# explorator_mainboard_v2_58mm.net
KiCad netlist of a schematic drawn in EAGLE
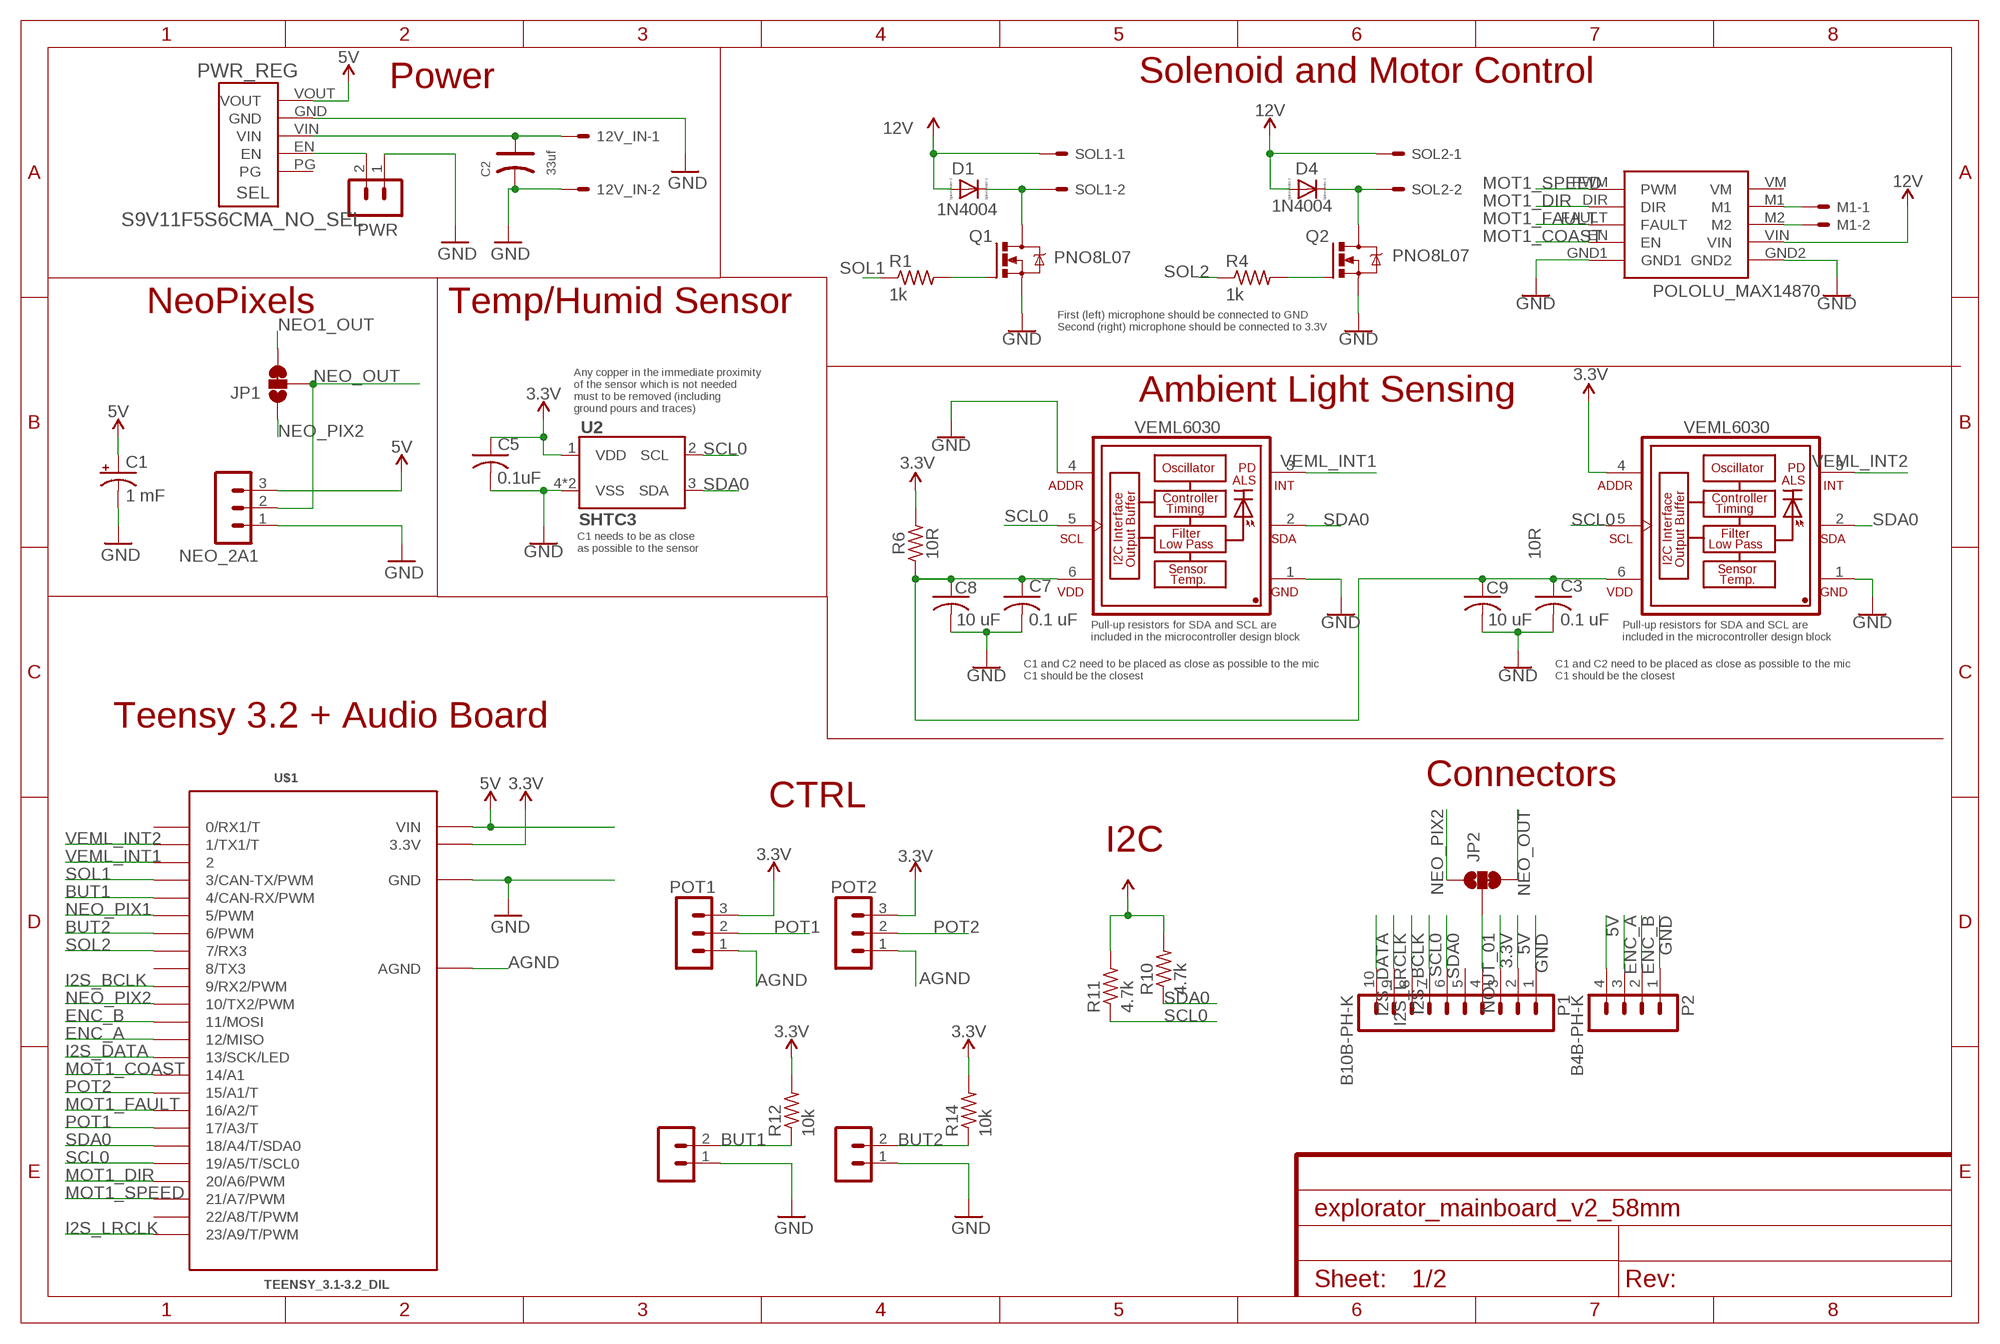
[diagram p0: schematic, sheet 1]
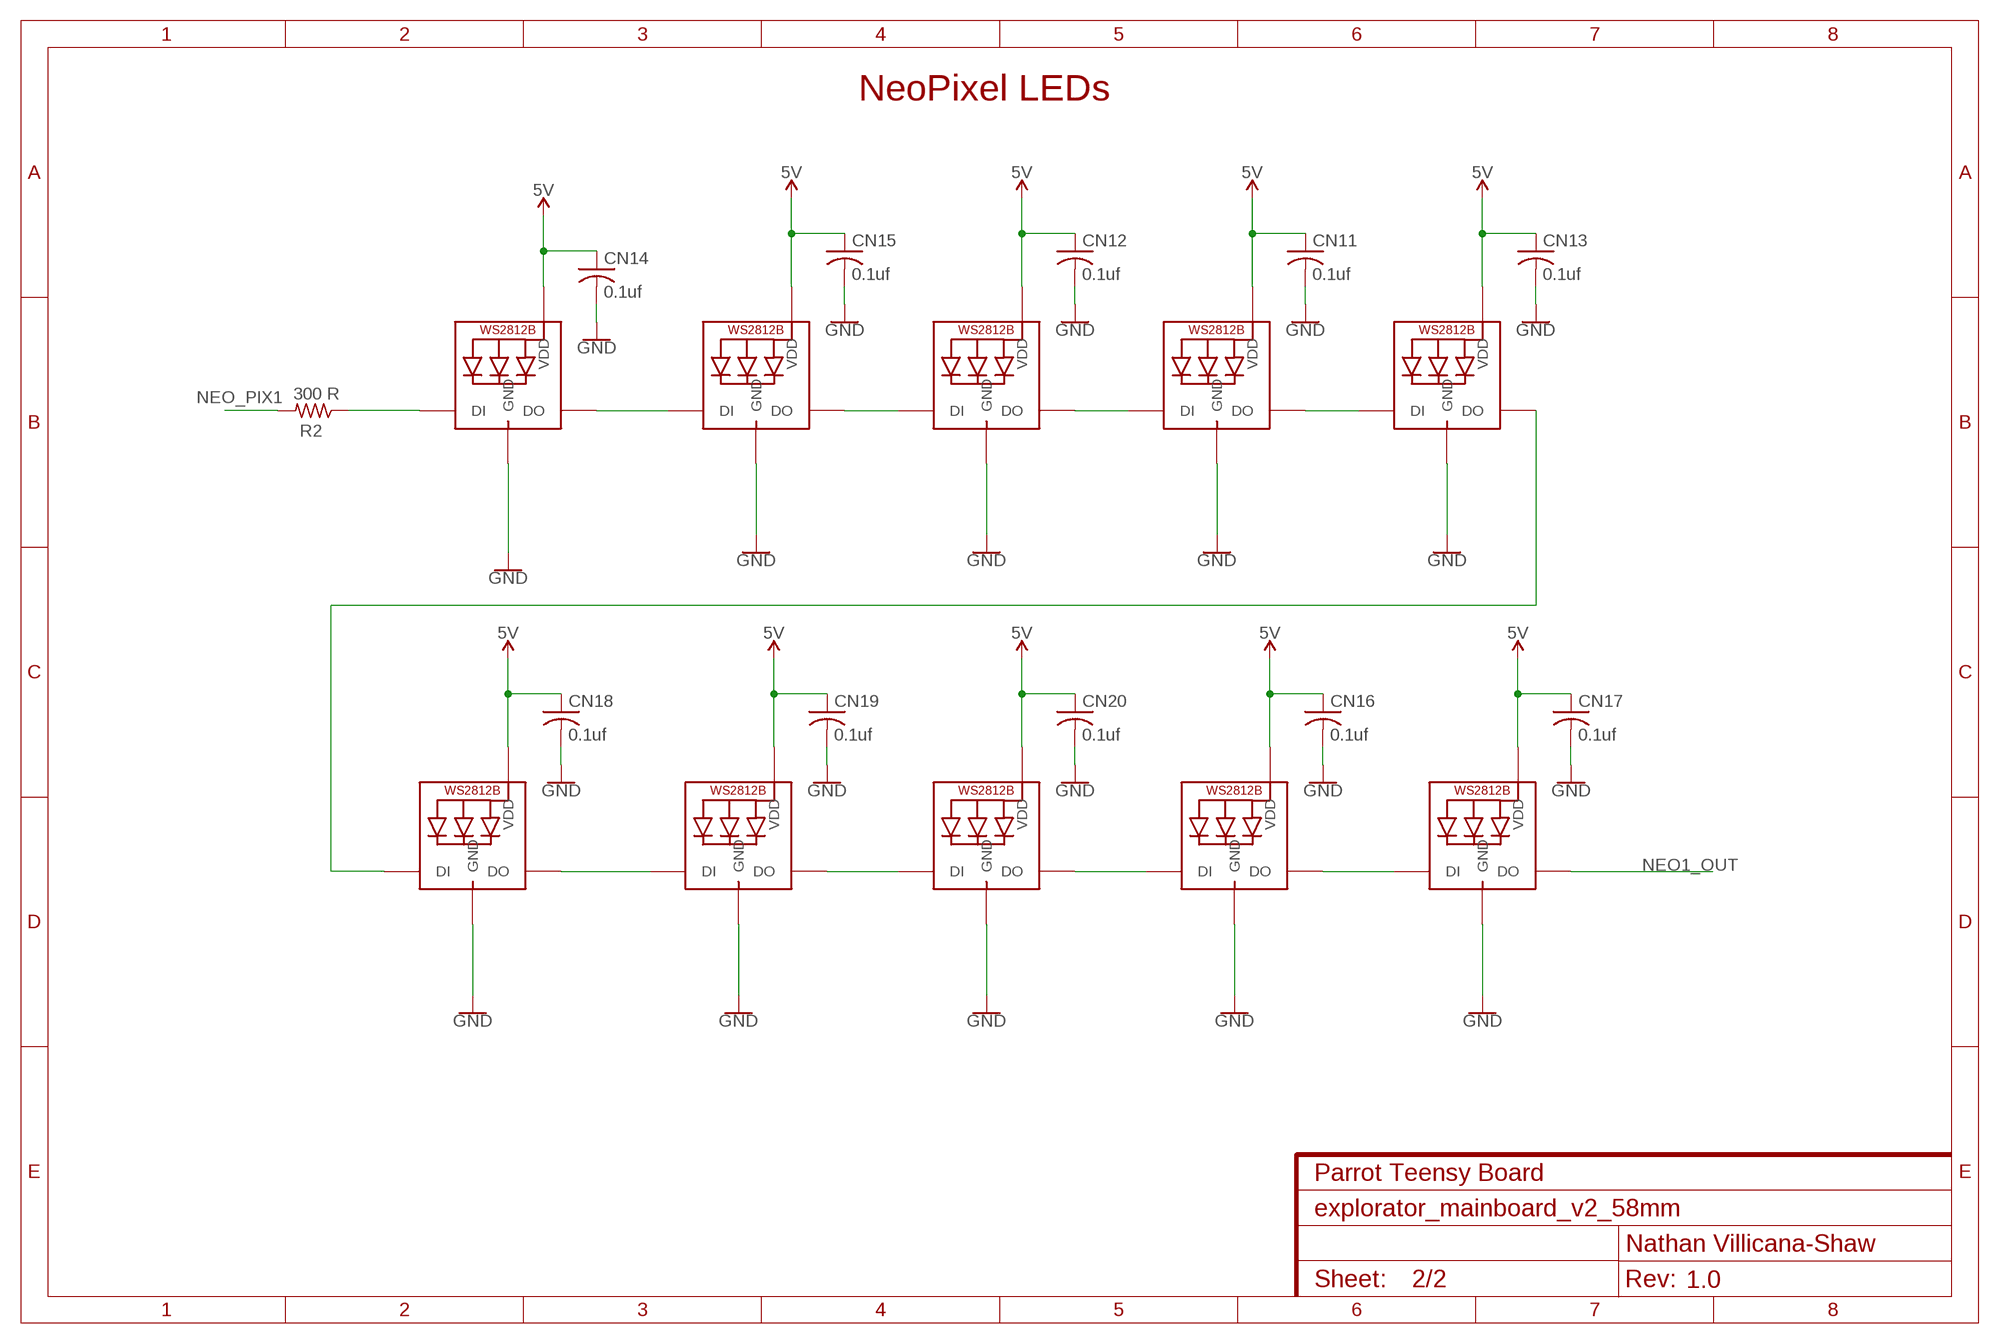
[diagram p1: schematic, sheet 2]

(export (version "E")
  (design (tool "Eeschema 10.0.6"))
  (components
    (comp (ref "12V_IN")
      (value "5566-2")
      (footprint "eagle-import:5566-2")
      (fields (field (name "MF") "MOLEX"))
      (libsource (lib "eagle-import") (part "5566-2"))
    )
    (comp (ref "BUT1")
      (value "B2B-PH-K")
      (footprint "eagle-import:B2B-PH-K")
      (libsource (lib "eagle-import") (part "B2B-PH-K"))
    )
    (comp (ref "BUT2")
      (value "B2B-PH-K")
      (footprint "eagle-import:B2B-PH-K")
      (libsource (lib "eagle-import") (part "B2B-PH-K"))
    )
    (comp (ref "C1")
      (value "1 mF")
      (footprint "eagle-import:UD-10X10_NICHICON")
      (libsource (lib "eagle-import") (part "CPOL-USUD-10X10"))
    )
    (comp (ref "C2")
      (value "33uf")
      (footprint "eagle-import:PC-D5.3MM")
      (fields (field (name "MPN") "KS 100uF/16V"))
      (libsource (lib "eagle-import") (part "DIP-ALUMINUM-47UF-16V(D5-H7MM)"))
    )
    (comp (ref "C3")
      (value "0.1 uF")
      (footprint "eagle-import:C0805")
      (libsource (lib "eagle-import") (part "C-USC0805"))
    )
    (comp (ref "C5")
      (value "0.1uF")
      (footprint "eagle-import:C0805")
      (libsource (lib "eagle-import") (part "C-USC0805"))
    )
    (comp (ref "C7")
      (value "0.1 uF")
      (footprint "eagle-import:C0805")
      (libsource (lib "eagle-import") (part "C-USC0805"))
    )
    (comp (ref "C8")
      (value "10 uF")
      (footprint "eagle-import:C0805")
      (libsource (lib "eagle-import") (part "C-USC0805"))
    )
    (comp (ref "C9")
      (value "10 uF")
      (footprint "eagle-import:C0805")
      (libsource (lib "eagle-import") (part "C-USC0805"))
    )
    (comp (ref "D1")
      (value "1N4004")
      (footprint "eagle-import:DIODE_DO35-7")
      (libsource (lib "eagle-import") (part "DIODE_E-DO35-7"))
    )
    (comp (ref "D4")
      (value "1N4004")
      (footprint "eagle-import:DIODE_DO35-7")
      (libsource (lib "eagle-import") (part "DIODE_E-DO35-7"))
    )
    (comp (ref "JP1")
      (value "JUMPER-SMT_3_1-NC_TRACE_SILK")
      (footprint "eagle-import:SMT-JUMPER_3_1-NC_TRACE_SILK")
      (libsource (lib "eagle-import") (part "JUMPER-SMT_3_1-NC_TRACE_SILK"))
    )
    (comp (ref "JP2")
      (value "JUMPER-SMT_3_1-NC_TRACE_SILK")
      (footprint "eagle-import:SMT-JUMPER_3_1-NC_TRACE_SILK")
      (libsource (lib "eagle-import") (part "JUMPER-SMT_3_1-NC_TRACE_SILK"))
    )
    (comp (ref "M1")
      (value "5566-2")
      (footprint "eagle-import:5566-2")
      (fields (field (name "MF") "MOLEX"))
      (libsource (lib "eagle-import") (part "5566-2"))
    )
    (comp (ref "MOT1")
      (value "POLOLU_MAX14870")
      (footprint "eagle-import:POLOLU_MAX14870")
      (libsource (lib "eagle-import") (part "POLOLU_MAX14870"))
    )
    (comp (ref "NEO_2A1")
      (value "B3B-PH-K")
      (footprint "eagle-import:B3B-PH-K")
      (libsource (lib "eagle-import") (part "B3B-PH-K"))
    )
    (comp (ref "P1")
      (value "B10B-PH-K")
      (footprint "eagle-import:B10B-PH-K")
      (libsource (lib "eagle-import") (part "B10B-PH-K"))
    )
    (comp (ref "P2")
      (value "B4B-PH-K")
      (footprint "eagle-import:B4B-PH-K")
      (libsource (lib "eagle-import") (part "B4B-PH-K"))
    )
    (comp (ref "POT1")
      (value "B3B-PH-K")
      (footprint "eagle-import:B3B-PH-K")
      (libsource (lib "eagle-import") (part "B3B-PH-K"))
    )
    (comp (ref "POT2")
      (value "B3B-PH-K")
      (footprint "eagle-import:B3B-PH-K")
      (libsource (lib "eagle-import") (part "B3B-PH-K"))
    )
    (comp (ref "PWR")
      (value "B2B-PH-K")
      (footprint "eagle-import:B2B-PH-K")
      (libsource (lib "eagle-import") (part "B2B-PH-K"))
    )
    (comp (ref "PWR_REG")
      (value "S9V11F5S6CMA_NO_SEL")
      (footprint "eagle-import:S9V11F3S5CMA_NO_SEL")
      (libsource (lib "eagle-import") (part "S9V11F5S6CMA_NO_SEL"))
    )
    (comp (ref "Q1")
      (value "PNO8L07")
      (footprint "eagle-import:TO220BV")
      (libsource (lib "eagle-import") (part "IRF540"))
    )
    (comp (ref "Q2")
      (value "PNO8L07")
      (footprint "eagle-import:TO220BV")
      (libsource (lib "eagle-import") (part "IRF540"))
    )
    (comp (ref "R1")
      (value "1k")
      (footprint "eagle-import:R0805")
      (libsource (lib "eagle-import") (part "rcl_334_R-US_R0805"))
    )
    (comp (ref "R4")
      (value "1k")
      (footprint "eagle-import:R0805")
      (libsource (lib "eagle-import") (part "rcl_334_R-US_R0805"))
    )
    (comp (ref "R6")
      (value "10 R")
      (footprint "eagle-import:R0805")
      (libsource (lib "eagle-import") (part "R-US_R0805"))
    )
    (comp (ref "R10")
      (value "4.7k")
      (footprint "eagle-import:R0805")
      (libsource (lib "eagle-import") (part "rcl_334_R-US_R0805"))
    )
    (comp (ref "R11")
      (value "4.7k")
      (footprint "eagle-import:R0805")
      (libsource (lib "eagle-import") (part "rcl_334_R-US_R0805"))
    )
    (comp (ref "R12")
      (value "10k")
      (footprint "eagle-import:R0805")
      (libsource (lib "eagle-import") (part "rcl_334_R-US_R0805"))
    )
    (comp (ref "R14")
      (value "10k")
      (footprint "eagle-import:R0805")
      (libsource (lib "eagle-import") (part "rcl_334_R-US_R0805"))
    )
    (comp (ref "SOL1")
      (value "5566-2")
      (footprint "eagle-import:5566-2")
      (fields (field (name "MF") "MOLEX"))
      (libsource (lib "eagle-import") (part "5566-2"))
    )
    (comp (ref "SOL2")
      (value "5566-2")
      (footprint "eagle-import:5566-2")
      (fields (field (name "MF") "MOLEX"))
      (libsource (lib "eagle-import") (part "5566-2"))
    )
    (comp (ref "U$1")
      (value "TEENSY_3.1-3.2_DIL")
      (footprint "eagle-import:TEENSY_3.0-3.2&LC_DIL")
      (libsource (lib "eagle-import") (part "TEENSY_3.1-3.2_DIL"))
    )
    (comp (ref "U2")
      (value "SHTC3")
      (footprint "eagle-import:SHTC3")
      (libsource (lib "eagle-import") (part "SHTC3"))
    )
    (comp (ref "VMEL1")
      (value "VEML6030")
      (footprint "eagle-import:VISHAY_VEML6030_2X2X0.87")
      (fields (field (name "MF") "Vishay Semiconductor") (field (name "MP") "VEML6030-GS15"))
      (libsource (lib "eagle-import") (part "VEML6030-GS15"))
    )
    (comp (ref "VMEL2")
      (value "VEML6030")
      (footprint "eagle-import:VISHAY_VEML6030_2X2X0.87")
      (fields (field (name "MF") "Vishay Semiconductor") (field (name "MP") "VEML6030-GS15"))
      (libsource (lib "eagle-import") (part "VEML6030-GS15"))
    )
    (comp (ref "CN11")
      (value "0.1uf")
      (footprint "eagle-import:C0805K")
      (libsource (lib "eagle-import") (part "resistor_348_C-USC0805K"))
    )
    (comp (ref "CN12")
      (value "0.1uf")
      (footprint "eagle-import:C0805K")
      (libsource (lib "eagle-import") (part "resistor_348_C-USC0805K"))
    )
    (comp (ref "CN13")
      (value "0.1uf")
      (footprint "eagle-import:C0805K")
      (libsource (lib "eagle-import") (part "resistor_348_C-USC0805K"))
    )
    (comp (ref "CN14")
      (value "0.1uf")
      (footprint "eagle-import:C0805K")
      (libsource (lib "eagle-import") (part "resistor_348_C-USC0805K"))
    )
    (comp (ref "CN15")
      (value "0.1uf")
      (footprint "eagle-import:C0805K")
      (libsource (lib "eagle-import") (part "resistor_348_C-USC0805K"))
    )
    (comp (ref "CN16")
      (value "0.1uf")
      (footprint "eagle-import:C0805K")
      (libsource (lib "eagle-import") (part "resistor_348_C-USC0805K"))
    )
    (comp (ref "CN17")
      (value "0.1uf")
      (footprint "eagle-import:C0805K")
      (libsource (lib "eagle-import") (part "resistor_348_C-USC0805K"))
    )
    (comp (ref "CN18")
      (value "0.1uf")
      (footprint "eagle-import:C0805K")
      (libsource (lib "eagle-import") (part "resistor_348_C-USC0805K"))
    )
    (comp (ref "CN19")
      (value "0.1uf")
      (footprint "eagle-import:C0805K")
      (libsource (lib "eagle-import") (part "resistor_348_C-USC0805K"))
    )
    (comp (ref "CN20")
      (value "0.1uf")
      (footprint "eagle-import:C0805K")
      (libsource (lib "eagle-import") (part "resistor_348_C-USC0805K"))
    )
    (comp (ref "NEO11")
      (value "WS2812B5050")
      (footprint "eagle-import:WS2812B")
      (libsource (lib "eagle-import") (part "WS2812B5050"))
    )
    (comp (ref "NEO12")
      (value "WS2812B5050")
      (footprint "eagle-import:WS2812B")
      (libsource (lib "eagle-import") (part "WS2812B5050"))
    )
    (comp (ref "NEO13")
      (value "WS2812B5050")
      (footprint "eagle-import:WS2812B")
      (libsource (lib "eagle-import") (part "WS2812B5050"))
    )
    (comp (ref "NEO14")
      (value "WS2812B5050")
      (footprint "eagle-import:WS2812B")
      (libsource (lib "eagle-import") (part "WS2812B5050"))
    )
    (comp (ref "NEO15")
      (value "WS2812B5050")
      (footprint "eagle-import:WS2812B")
      (libsource (lib "eagle-import") (part "WS2812B5050"))
    )
    (comp (ref "NEO16")
      (value "WS2812B5050")
      (footprint "eagle-import:WS2812B")
      (libsource (lib "eagle-import") (part "WS2812B5050"))
    )
    (comp (ref "NEO17")
      (value "WS2812B5050")
      (footprint "eagle-import:WS2812B")
      (libsource (lib "eagle-import") (part "WS2812B5050"))
    )
    (comp (ref "NEO18")
      (value "WS2812B5050")
      (footprint "eagle-import:WS2812B")
      (libsource (lib "eagle-import") (part "WS2812B5050"))
    )
    (comp (ref "NEO19")
      (value "WS2812B5050")
      (footprint "eagle-import:WS2812B")
      (libsource (lib "eagle-import") (part "WS2812B5050"))
    )
    (comp (ref "NEO20")
      (value "WS2812B5050")
      (footprint "eagle-import:WS2812B")
      (libsource (lib "eagle-import") (part "WS2812B5050"))
    )
    (comp (ref "R2")
      (value "300 R")
      (footprint "eagle-import:R0805")
      (libsource (lib "eagle-import") (part "R-US_R0805"))
    )
  )
  (nets
    (net (code "1") (name "3.3V") (class "Default")
      (node (ref "C5") (pin "1") (pinfunction "1_1") (pintype "passive"))
      (node (ref "P1") (pin "3") (pinfunction "3_3") (pintype "passive"))
      (node (ref "POT1") (pin "3") (pinfunction "3_3") (pintype "passive"))
      (node (ref "POT2") (pin "3") (pinfunction "3_3") (pintype "passive"))
      (node (ref "R10") (pin "2") (pinfunction "2_2") (pintype "passive"))
      (node (ref "R11") (pin "2") (pinfunction "2_2") (pintype "passive"))
      (node (ref "R12") (pin "2") (pinfunction "2_2") (pintype "passive"))
      (node (ref "R14") (pin "2") (pinfunction "2_2") (pintype "passive"))
      (node (ref "R6") (pin "2") (pinfunction "2_2") (pintype "passive"))
      (node (ref "U$1") (pin "3.3V") (pinfunction "3.3V_3.3V") (pintype "power_in"))
      (node (ref "U2") (pin "1") (pinfunction "VDD_1") (pintype "bidirectional"))
      (node (ref "VMEL2") (pin "4") (pinfunction "ADDR_4") (pintype "bidirectional"))
    )
    (net (code "2") (name "5V") (class "Default")
      (node (ref "C1") (pin "+") (pinfunction "+_+") (pintype "passive"))
      (node (ref "CN11") (pin "1") (pinfunction "1_1") (pintype "passive"))
      (node (ref "CN12") (pin "1") (pinfunction "1_1") (pintype "passive"))
      (node (ref "CN13") (pin "1") (pinfunction "1_1") (pintype "passive"))
      (node (ref "CN14") (pin "1") (pinfunction "1_1") (pintype "passive"))
      (node (ref "CN15") (pin "1") (pinfunction "1_1") (pintype "passive"))
      (node (ref "CN16") (pin "1") (pinfunction "1_1") (pintype "passive"))
      (node (ref "CN17") (pin "1") (pinfunction "1_1") (pintype "passive"))
      (node (ref "CN18") (pin "1") (pinfunction "1_1") (pintype "passive"))
      (node (ref "CN19") (pin "1") (pinfunction "1_1") (pintype "passive"))
      (node (ref "CN20") (pin "1") (pinfunction "1_1") (pintype "passive"))
      (node (ref "NEO11") (pin "1-VDD") (pinfunction "VDD_1-VDD") (pintype "power_in"))
      (node (ref "NEO12") (pin "1-VDD") (pinfunction "VDD_1-VDD") (pintype "power_in"))
      (node (ref "NEO13") (pin "1-VDD") (pinfunction "VDD_1-VDD") (pintype "power_in"))
      (node (ref "NEO14") (pin "1-VDD") (pinfunction "VDD_1-VDD") (pintype "power_in"))
      (node (ref "NEO15") (pin "1-VDD") (pinfunction "VDD_1-VDD") (pintype "power_in"))
      (node (ref "NEO16") (pin "1-VDD") (pinfunction "VDD_1-VDD") (pintype "power_in"))
      (node (ref "NEO17") (pin "1-VDD") (pinfunction "VDD_1-VDD") (pintype "power_in"))
      (node (ref "NEO18") (pin "1-VDD") (pinfunction "VDD_1-VDD") (pintype "power_in"))
      (node (ref "NEO19") (pin "1-VDD") (pinfunction "VDD_1-VDD") (pintype "power_in"))
      (node (ref "NEO20") (pin "1-VDD") (pinfunction "VDD_1-VDD") (pintype "power_in"))
      (node (ref "NEO_2A1") (pin "3") (pinfunction "3_3") (pintype "passive"))
      (node (ref "P1") (pin "2") (pinfunction "2_2") (pintype "passive"))
      (node (ref "P2") (pin "4") (pinfunction "4_4") (pintype "passive"))
      (node (ref "PWR_REG") (pin "VOUT") (pinfunction "VOUT_VOUT") (pintype "bidirectional"))
      (node (ref "U$1") (pin "VIN") (pinfunction "VIN_VIN") (pintype "power_in"))
    )
    (net (code "3") (name "12V") (class "Default")
      (node (ref "12V_IN") (pin "1") (pinfunction "S_1") (pintype "passive"))
      (node (ref "C2") (pin "+") (pinfunction "+_+") (pintype "passive"))
      (node (ref "D1") (pin "A") (pinfunction "C_A") (pintype "passive"))
      (node (ref "D4") (pin "A") (pinfunction "C_A") (pintype "passive"))
      (node (ref "MOT1") (pin "VIN") (pinfunction "VIN_VIN") (pintype "bidirectional"))
      (node (ref "PWR_REG") (pin "VIN") (pinfunction "VIN_VIN") (pintype "bidirectional"))
      (node (ref "SOL1") (pin "1") (pinfunction "S_1") (pintype "passive"))
      (node (ref "SOL2") (pin "1") (pinfunction "S_1") (pintype "passive"))
    )
    (net (code "4") (name "AGND") (class "Default")
      (node (ref "POT1") (pin "1") (pinfunction "1_1") (pintype "passive"))
      (node (ref "POT2") (pin "1") (pinfunction "1_1") (pintype "passive"))
      (node (ref "U$1") (pin "AGND") (pinfunction "AGND_AGND") (pintype "power_in"))
    )
    (net (code "5") (name "BUT1") (class "Default")
      (node (ref "BUT1") (pin "2") (pinfunction "2_2") (pintype "passive"))
      (node (ref "R12") (pin "1") (pinfunction "1_1") (pintype "passive"))
      (node (ref "U$1") (pin "4") (pinfunction "4/CAN-RX/PWM_4") (pintype "bidirectional"))
    )
    (net (code "6") (name "BUT2") (class "Default")
      (node (ref "BUT2") (pin "2") (pinfunction "2_2") (pintype "passive"))
      (node (ref "R14") (pin "1") (pinfunction "1_1") (pintype "passive"))
      (node (ref "U$1") (pin "6") (pinfunction "6/PWM_6") (pintype "bidirectional"))
    )
    (net (code "7") (name "ENC_A") (class "Default")
      (node (ref "P2") (pin "3") (pinfunction "3_3") (pintype "passive"))
      (node (ref "U$1") (pin "12") (pinfunction "12/MISO_12") (pintype "bidirectional"))
    )
    (net (code "8") (name "ENC_B") (class "Default")
      (node (ref "P2") (pin "2") (pinfunction "2_2") (pintype "passive"))
      (node (ref "U$1") (pin "11") (pinfunction "11/MOSI_11") (pintype "bidirectional"))
    )
    (net (code "9") (name "GND") (class "Default")
      (node (ref "12V_IN") (pin "2") (pinfunction "S_2") (pintype "passive"))
      (node (ref "BUT1") (pin "1") (pinfunction "1_1") (pintype "passive"))
      (node (ref "BUT2") (pin "1") (pinfunction "1_1") (pintype "passive"))
      (node (ref "C1") (pin "-") (pinfunction "-_-") (pintype "passive"))
      (node (ref "C2") (pin "-") (pinfunction "-_-") (pintype "passive"))
      (node (ref "C3") (pin "2") (pinfunction "2_2") (pintype "passive"))
      (node (ref "C5") (pin "2") (pinfunction "2_2") (pintype "passive"))
      (node (ref "C7") (pin "2") (pinfunction "2_2") (pintype "passive"))
      (node (ref "C8") (pin "2") (pinfunction "2_2") (pintype "passive"))
      (node (ref "C9") (pin "2") (pinfunction "2_2") (pintype "passive"))
      (node (ref "CN11") (pin "2") (pinfunction "2_2") (pintype "passive"))
      (node (ref "CN12") (pin "2") (pinfunction "2_2") (pintype "passive"))
      (node (ref "CN13") (pin "2") (pinfunction "2_2") (pintype "passive"))
      (node (ref "CN14") (pin "2") (pinfunction "2_2") (pintype "passive"))
      (node (ref "CN15") (pin "2") (pinfunction "2_2") (pintype "passive"))
      (node (ref "CN16") (pin "2") (pinfunction "2_2") (pintype "passive"))
      (node (ref "CN17") (pin "2") (pinfunction "2_2") (pintype "passive"))
      (node (ref "CN18") (pin "2") (pinfunction "2_2") (pintype "passive"))
      (node (ref "CN19") (pin "2") (pinfunction "2_2") (pintype "passive"))
      (node (ref "CN20") (pin "2") (pinfunction "2_2") (pintype "passive"))
      (node (ref "MOT1") (pin "GND1") (pinfunction "GND1_GND1") (pintype "bidirectional"))
      (node (ref "MOT1") (pin "GND2") (pinfunction "GND2_GND2") (pintype "bidirectional"))
      (node (ref "NEO11") (pin "3-GND") (pinfunction "GND_3-GND") (pintype "power_in"))
      (node (ref "NEO12") (pin "3-GND") (pinfunction "GND_3-GND") (pintype "power_in"))
      (node (ref "NEO13") (pin "3-GND") (pinfunction "GND_3-GND") (pintype "power_in"))
      (node (ref "NEO14") (pin "3-GND") (pinfunction "GND_3-GND") (pintype "power_in"))
      (node (ref "NEO15") (pin "3-GND") (pinfunction "GND_3-GND") (pintype "power_in"))
      (node (ref "NEO16") (pin "3-GND") (pinfunction "GND_3-GND") (pintype "power_in"))
      (node (ref "NEO17") (pin "3-GND") (pinfunction "GND_3-GND") (pintype "power_in"))
      (node (ref "NEO18") (pin "3-GND") (pinfunction "GND_3-GND") (pintype "power_in"))
      (node (ref "NEO19") (pin "3-GND") (pinfunction "GND_3-GND") (pintype "power_in"))
      (node (ref "NEO20") (pin "3-GND") (pinfunction "GND_3-GND") (pintype "power_in"))
      (node (ref "NEO_2A1") (pin "1") (pinfunction "1_1") (pintype "passive"))
      (node (ref "P1") (pin "1") (pinfunction "1_1") (pintype "passive"))
      (node (ref "P2") (pin "1") (pinfunction "1_1") (pintype "passive"))
      (node (ref "PWR") (pin "1") (pinfunction "1_1") (pintype "passive"))
      (node (ref "PWR_REG") (pin "GND") (pinfunction "GND_GND") (pintype "bidirectional"))
      (node (ref "Q1") (pin "S") (pinfunction "S_S") (pintype "passive"))
      (node (ref "Q2") (pin "S") (pinfunction "S_S") (pintype "passive"))
      (node (ref "U$1") (pin "GND") (pinfunction "GND_GND") (pintype "power_in"))
      (node (ref "U2") (pin "4") (pinfunction "VSS_4") (pintype "bidirectional"))
      (node (ref "U2") (pin "5") (pinfunction "VSS_5") (pintype "bidirectional"))
      (node (ref "VMEL1") (pin "1") (pinfunction "GND_1") (pintype "power_in"))
      (node (ref "VMEL1") (pin "4") (pinfunction "ADDR_4") (pintype "bidirectional"))
      (node (ref "VMEL2") (pin "1") (pinfunction "GND_1") (pintype "power_in"))
    )
    (net (code "10") (name "I2S_BCLK") (class "Default")
      (node (ref "P1") (pin "8") (pinfunction "8_8") (pintype "passive"))
      (node (ref "U$1") (pin "9") (pinfunction "9/RX2/PWM_9") (pintype "bidirectional"))
    )
    (net (code "11") (name "I2S_DATA") (class "Default")
      (node (ref "P1") (pin "10") (pinfunction "10_10") (pintype "passive"))
      (node (ref "U$1") (pin "13") (pinfunction "13/SCK/LED_13") (pintype "bidirectional"))
    )
    (net (code "12") (name "I2S_LRCLK") (class "Default")
      (node (ref "P1") (pin "9") (pinfunction "9_9") (pintype "passive"))
      (node (ref "U$1") (pin "23/A9") (pinfunction "23/A9/T/PWM_23/A9") (pintype "bidirectional"))
    )
    (net (code "13") (name "MOT1_COAST") (class "Default")
      (node (ref "MOT1") (pin "EN") (pinfunction "EN_EN") (pintype "bidirectional"))
      (node (ref "U$1") (pin "14/A0") (pinfunction "14/A1_14/A0") (pintype "bidirectional"))
    )
    (net (code "14") (name "MOT1_DIR") (class "Default")
      (node (ref "MOT1") (pin "DIR") (pinfunction "DIR_DIR") (pintype "bidirectional"))
      (node (ref "U$1") (pin "20/A6") (pinfunction "20/A6/PWM_20/A6") (pintype "bidirectional"))
    )
    (net (code "15") (name "MOT1_FAULT") (class "Default")
      (node (ref "MOT1") (pin "FAULT") (pinfunction "FAULT_FAULT") (pintype "bidirectional"))
      (node (ref "U$1") (pin "16/A2") (pinfunction "16/A2/T_16/A2") (pintype "bidirectional"))
    )
    (net (code "16") (name "MOT1_SPEED") (class "Default")
      (node (ref "MOT1") (pin "PWM") (pinfunction "PWM_PWM") (pintype "bidirectional"))
      (node (ref "U$1") (pin "21/A7") (pinfunction "21/A7/PWM_21/A7") (pintype "bidirectional"))
    )
    (net (code "17") (name "NEO1_OUT") (class "Default")
      (node (ref "JP1") (pin "3") (pinfunction "3_3") (pintype "passive"))
      (node (ref "NEO17") (pin "2-DOUT") (pinfunction "DO_2-DOUT") (pintype "output"))
    )
    (net (code "18") (name "NEO_OUT") (class "Default")
      (node (ref "JP1") (pin "2") (pinfunction "2_2") (pintype "passive"))
      (node (ref "JP2") (pin "3") (pinfunction "3_3") (pintype "passive"))
      (node (ref "NEO_2A1") (pin "2") (pinfunction "2_2") (pintype "passive"))
    )
    (net (code "19") (name "NEO_PIX1") (class "Default")
      (node (ref "R2") (pin "2") (pinfunction "2_2") (pintype "passive"))
      (node (ref "U$1") (pin "5") (pinfunction "5/PWM_5") (pintype "bidirectional"))
    )
    (net (code "20") (name "NEO_PIX2") (class "Default")
      (node (ref "JP1") (pin "1") (pinfunction "1_1") (pintype "passive"))
      (node (ref "JP2") (pin "1") (pinfunction "1_1") (pintype "passive"))
      (node (ref "U$1") (pin "10") (pinfunction "10/TX2/PWM_10") (pintype "bidirectional"))
    )
    (net (code "21") (name "NOUT_01") (class "Default")
      (node (ref "JP2") (pin "2") (pinfunction "2_2") (pintype "passive"))
      (node (ref "P1") (pin "4") (pinfunction "4_4") (pintype "passive"))
    )
    (net (code "22") (name "Net-(D1-A)") (class "Default")
      (node (ref "D1") (pin "C") (pinfunction "A_C") (pintype "passive"))
      (node (ref "Q1") (pin "D") (pinfunction "D_D") (pintype "passive"))
      (node (ref "SOL1") (pin "2") (pinfunction "S_2") (pintype "passive"))
    )
    (net (code "23") (name "Net-(D4-A)") (class "Default")
      (node (ref "D4") (pin "C") (pinfunction "A_C") (pintype "passive"))
      (node (ref "Q2") (pin "D") (pinfunction "D_D") (pintype "passive"))
      (node (ref "SOL2") (pin "2") (pinfunction "S_2") (pintype "passive"))
    )
    (net (code "24") (name "Net-(M1A-S)") (class "Default")
      (node (ref "M1") (pin "1") (pinfunction "S_1") (pintype "passive"))
      (node (ref "MOT1") (pin "M1") (pinfunction "M1_M1") (pintype "bidirectional"))
    )
    (net (code "25") (name "Net-(M1B-S)") (class "Default")
      (node (ref "M1") (pin "2") (pinfunction "S_2") (pintype "passive"))
      (node (ref "MOT1") (pin "M2") (pinfunction "M2_M2") (pintype "bidirectional"))
    )
    (net (code "26") (name "Net-(NEO11-DI)") (class "Default")
      (node (ref "NEO11") (pin "4-DIN") (pinfunction "DI_4-DIN") (pintype "input"))
      (node (ref "NEO12") (pin "2-DOUT") (pinfunction "DO_2-DOUT") (pintype "output"))
    )
    (net (code "27") (name "Net-(NEO11-DO)") (class "Default")
      (node (ref "NEO11") (pin "2-DOUT") (pinfunction "DO_2-DOUT") (pintype "output"))
      (node (ref "NEO13") (pin "4-DIN") (pinfunction "DI_4-DIN") (pintype "input"))
    )
    (net (code "28") (name "Net-(NEO12-DI)") (class "Default")
      (node (ref "NEO12") (pin "4-DIN") (pinfunction "DI_4-DIN") (pintype "input"))
      (node (ref "NEO15") (pin "2-DOUT") (pinfunction "DO_2-DOUT") (pintype "output"))
    )
    (net (code "29") (name "Net-(NEO13-DO)") (class "Default")
      (node (ref "NEO13") (pin "2-DOUT") (pinfunction "DO_2-DOUT") (pintype "output"))
      (node (ref "NEO18") (pin "4-DIN") (pinfunction "DI_4-DIN") (pintype "input"))
    )
    (net (code "30") (name "Net-(NEO14-DI)") (class "Default")
      (node (ref "NEO14") (pin "4-DIN") (pinfunction "DI_4-DIN") (pintype "input"))
      (node (ref "R2") (pin "1") (pinfunction "1_1") (pintype "passive"))
    )
    (net (code "31") (name "Net-(NEO14-DO)") (class "Default")
      (node (ref "NEO14") (pin "2-DOUT") (pinfunction "DO_2-DOUT") (pintype "output"))
      (node (ref "NEO15") (pin "4-DIN") (pinfunction "DI_4-DIN") (pintype "input"))
    )
    (net (code "32") (name "Net-(NEO16-DI)") (class "Default")
      (node (ref "NEO16") (pin "4-DIN") (pinfunction "DI_4-DIN") (pintype "input"))
      (node (ref "NEO20") (pin "2-DOUT") (pinfunction "DO_2-DOUT") (pintype "output"))
    )
    (net (code "33") (name "Net-(NEO16-DO)") (class "Default")
      (node (ref "NEO16") (pin "2-DOUT") (pinfunction "DO_2-DOUT") (pintype "output"))
      (node (ref "NEO17") (pin "4-DIN") (pinfunction "DI_4-DIN") (pintype "input"))
    )
    (net (code "34") (name "Net-(NEO18-DO)") (class "Default")
      (node (ref "NEO18") (pin "2-DOUT") (pinfunction "DO_2-DOUT") (pintype "output"))
      (node (ref "NEO19") (pin "4-DIN") (pinfunction "DI_4-DIN") (pintype "input"))
    )
    (net (code "35") (name "Net-(NEO19-DO)") (class "Default")
      (node (ref "NEO19") (pin "2-DOUT") (pinfunction "DO_2-DOUT") (pintype "output"))
      (node (ref "NEO20") (pin "4-DIN") (pinfunction "DI_4-DIN") (pintype "input"))
    )
    (net (code "36") (name "Net-(PWR-Pad2)") (class "Default")
      (node (ref "PWR") (pin "2") (pinfunction "2_2") (pintype "passive"))
      (node (ref "PWR_REG") (pin "EN") (pinfunction "EN_EN") (pintype "bidirectional"))
    )
    (net (code "37") (name "Net-(Q1-PadG)") (class "Default")
      (node (ref "Q1") (pin "G") (pinfunction "G_G") (pintype "passive"))
      (node (ref "R1") (pin "2") (pinfunction "2_2") (pintype "passive"))
    )
    (net (code "38") (name "Net-(Q2-PadG)") (class "Default")
      (node (ref "Q2") (pin "G") (pinfunction "G_G") (pintype "passive"))
      (node (ref "R4") (pin "2") (pinfunction "2_2") (pintype "passive"))
    )
    (net (code "39") (name "Net-(VMEL1-VDD)") (class "Default")
      (node (ref "C3") (pin "1") (pinfunction "1_1") (pintype "passive"))
      (node (ref "C7") (pin "1") (pinfunction "1_1") (pintype "passive"))
      (node (ref "C8") (pin "1") (pinfunction "1_1") (pintype "passive"))
      (node (ref "C9") (pin "1") (pinfunction "1_1") (pintype "passive"))
      (node (ref "R6") (pin "1") (pinfunction "1_1") (pintype "passive"))
      (node (ref "VMEL1") (pin "6") (pinfunction "VDD_6") (pintype "power_in"))
      (node (ref "VMEL2") (pin "6") (pinfunction "VDD_6") (pintype "power_in"))
    )
    (net (code "40") (name "POT1") (class "Default")
      (node (ref "POT1") (pin "2") (pinfunction "2_2") (pintype "passive"))
      (node (ref "U$1") (pin "17/A3") (pinfunction "17/A3/T_17/A3") (pintype "bidirectional"))
    )
    (net (code "41") (name "POT2") (class "Default")
      (node (ref "POT2") (pin "2") (pinfunction "2_2") (pintype "passive"))
      (node (ref "U$1") (pin "15/A1") (pinfunction "15/A1/T_15/A1") (pintype "bidirectional"))
    )
    (net (code "42") (name "SCL0") (class "Default")
      (node (ref "P1") (pin "7") (pinfunction "7_7") (pintype "passive"))
      (node (ref "R11") (pin "1") (pinfunction "1_1") (pintype "passive"))
      (node (ref "U$1") (pin "19/A5") (pinfunction "19/A5/T/SCL0_19/A5") (pintype "bidirectional"))
      (node (ref "U2") (pin "2") (pinfunction "SCL_2") (pintype "bidirectional"))
      (node (ref "VMEL1") (pin "5") (pinfunction "SCL_5") (pintype "input"))
      (node (ref "VMEL2") (pin "5") (pinfunction "SCL_5") (pintype "input"))
    )
    (net (code "43") (name "SDA0") (class "Default")
      (node (ref "P1") (pin "6") (pinfunction "6_6") (pintype "passive"))
      (node (ref "R10") (pin "1") (pinfunction "1_1") (pintype "passive"))
      (node (ref "U$1") (pin "18/A4") (pinfunction "18/A4/T/SDA0_18/A4") (pintype "bidirectional"))
      (node (ref "U2") (pin "3") (pinfunction "SDA_3") (pintype "bidirectional"))
      (node (ref "VMEL1") (pin "2") (pinfunction "SDA_2") (pintype "bidirectional"))
      (node (ref "VMEL2") (pin "2") (pinfunction "SDA_2") (pintype "bidirectional"))
    )
    (net (code "44") (name "SOL1") (class "Default")
      (node (ref "R1") (pin "1") (pinfunction "1_1") (pintype "passive"))
      (node (ref "U$1") (pin "3") (pinfunction "3/CAN-TX/PWM_3") (pintype "bidirectional"))
    )
    (net (code "45") (name "SOL2") (class "Default")
      (node (ref "R4") (pin "1") (pinfunction "1_1") (pintype "passive"))
      (node (ref "U$1") (pin "7") (pinfunction "7/RX3_7") (pintype "bidirectional"))
    )
    (net (code "46") (name "VEML_INT1") (class "Default")
      (node (ref "U$1") (pin "2") (pinfunction "2_2") (pintype "bidirectional"))
      (node (ref "VMEL1") (pin "3") (pinfunction "INT_3") (pintype "output"))
    )
    (net (code "47") (name "VEML_INT2") (class "Default")
      (node (ref "U$1") (pin "1") (pinfunction "1/TX1/T_1") (pintype "bidirectional"))
      (node (ref "VMEL2") (pin "3") (pinfunction "INT_3") (pintype "output"))
    )
    (net (code "48") (name "unconnected-(MOT1-PadVM)") (class "Default")
      (node (ref "MOT1") (pin "VM") (pinfunction "VM_VM") (pintype "bidirectional"))
    )
    (net (code "49") (name "unconnected-(P1-Pad5)") (class "Default")
      (node (ref "P1") (pin "5") (pinfunction "5_5") (pintype "passive"))
    )
    (net (code "50") (name "unconnected-(PWR_REG-PadPG)") (class "Default")
      (node (ref "PWR_REG") (pin "PG") (pinfunction "PG_PG") (pintype "bidirectional"))
    )
    (net (code "51") (name "unconnected-(U$1-0{slash}RX1{slash}T-Pad0)") (class "Default")
      (node (ref "U$1") (pin "0") (pinfunction "0/RX1/T_0") (pintype "bidirectional"))
    )
    (net (code "52") (name "unconnected-(U$1-8{slash}TX3-Pad8)") (class "Default")
      (node (ref "U$1") (pin "8") (pinfunction "8/TX3_8") (pintype "bidirectional"))
    )
    (net (code "53") (name "unconnected-(U$1-22{slash}A8{slash}T{slash}PWM-Pad22{slash}A8)") (class "Default")
      (node (ref "U$1") (pin "22/A8") (pinfunction "22/A8/T/PWM_22/A8") (pintype "bidirectional"))
    )
  )
)
